# comm.net
KiCad netlist of a schematic drawn in EAGLE
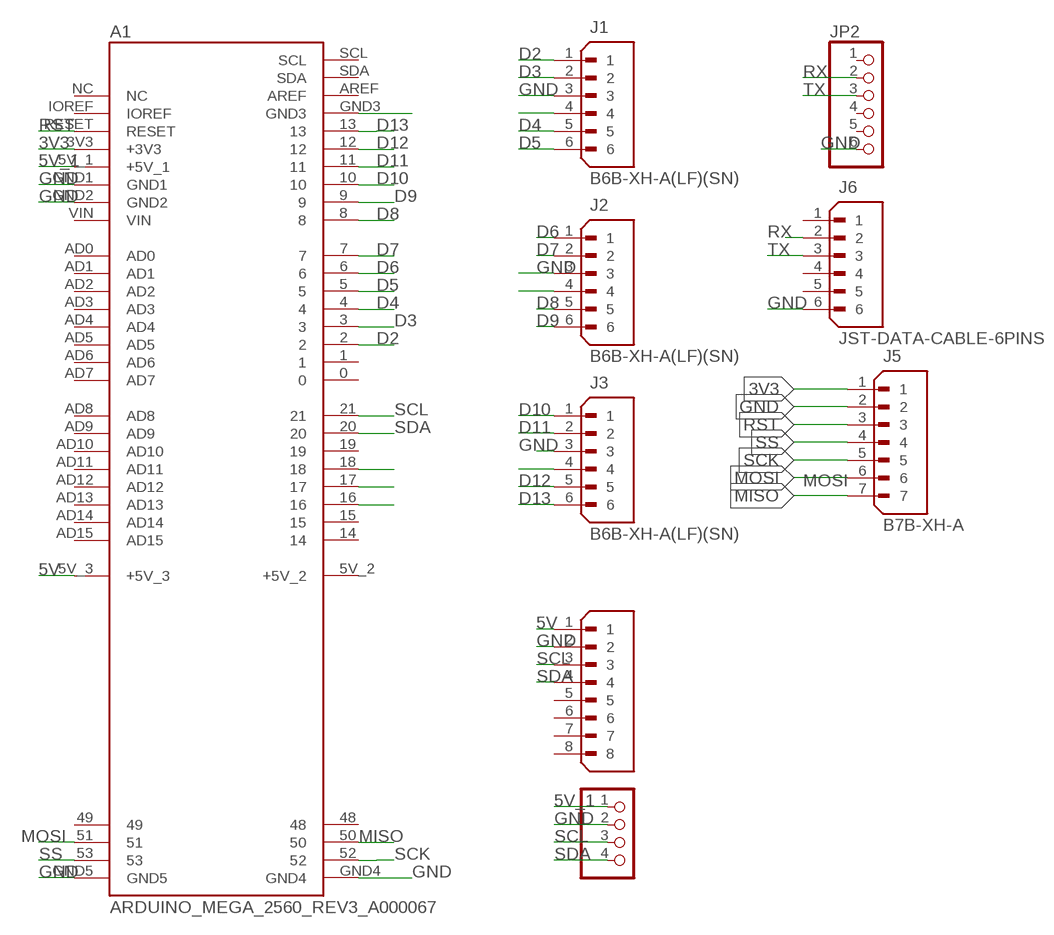
[diagram p0: schematic, sheet 1]

(export (version "E")
  (design (tool "Eeschema 10.0.6"))
  (components
    (comp (ref "A1")
      (value "ARDUINO_MEGA_2560_REV3_A000067")
      (footprint "eagle-import:ARDUINO_ARDUINO_MEGA_2560_REV3_A000067")
      (fields (field (name "MF") "Arduino") (field (name "MP") "ARDUINO MEGA 2560 REV3 | A000067"))
      (libsource (lib "eagle-import") (part "ARDUINO_MEGA_2560_REV3_A000067"))
    )
    (comp (ref "J1")
      (value "B6B-XH-A(LF)(SN)")
      (footprint "eagle-import:JST_B6B-XH-A(LF)(SN)")
      (fields (field (name "MF") "JST Sales") (field (name "MP") "B6B-XH-A (LF)(SN)"))
      (libsource (lib "eagle-import") (part "B6B-XH-A(LF)(SN)"))
    )
    (comp (ref "J2")
      (value "B6B-XH-A(LF)(SN)")
      (footprint "eagle-import:JST_B6B-XH-A(LF)(SN)")
      (fields (field (name "MF") "JST Sales") (field (name "MP") "B6B-XH-A (LF)(SN)"))
      (libsource (lib "eagle-import") (part "B6B-XH-A(LF)(SN)"))
    )
    (comp (ref "J3")
      (value "B6B-XH-A(LF)(SN)")
      (footprint "eagle-import:JST_B6B-XH-A(LF)(SN)")
      (fields (field (name "MF") "JST Sales") (field (name "MP") "B6B-XH-A (LF)(SN)"))
      (libsource (lib "eagle-import") (part "B6B-XH-A(LF)(SN)"))
    )
    (comp (ref "J4")
      (value "B8B-XH-A(LF)(SN)")
      (footprint "eagle-import:JST_B8B-XH-A(LF)(SN)")
      (fields (field (name "MF") "JST Sales") (field (name "MP") "B8B-XH-A (LF)(SN)"))
      (libsource (lib "eagle-import") (part "B8B-XH-A(LF)(SN)"))
    )
    (comp (ref "J5")
      (value "B7B-XH-A")
      (footprint "eagle-import:JST_B7B-XH-A")
      (fields (field (name "MF") "JST Sales"))
      (libsource (lib "eagle-import") (part "B7B-XH-A"))
    )
    (comp (ref "J6")
      (value "JST-DATA-CABLE-6PINS")
      (footprint "eagle-import:JST_B6B-XH-A(LF)(SN)")
      (fields (field (name "MF") "JST Sales") (field (name "MP") "B6B-XH-A (LF)(SN)"))
      (libsource (lib "eagle-import") (part "JST-DATA-CABLE-6PINS"))
    )
    (comp (ref "JP1")
      (value "PINHD-1X4")
      (footprint "eagle-import:1X04")
      (libsource (lib "eagle-import") (part "PINHD-1X4"))
    )
    (comp (ref "JP2")
      (value "PINHD-1X6")
      (footprint "eagle-import:1X06")
      (libsource (lib "eagle-import") (part "PINHD-1X6"))
    )
  )
  (nets
    (net (code "1") (name "/5V") (class "Default")
      (node (ref "A1") (pin "5V_3") (pinfunction "+5V_3_5V_3") (pintype "passive"))
      (node (ref "J4") (pin "1") (pinfunction "1_1") (pintype "passive"))
    )
    (net (code "2") (name "/5V_1") (class "Default")
      (node (ref "A1") (pin "5V_1") (pinfunction "+5V_1_5V_1") (pintype "passive"))
      (node (ref "JP1") (pin "1") (pinfunction "1_1") (pintype "passive"))
    )
    (net (code "3") (name "/D2") (class "Default")
      (node (ref "A1") (pin "2") (pinfunction "2_2") (pintype "passive"))
      (node (ref "J1") (pin "1") (pinfunction "1_1") (pintype "passive"))
    )
    (net (code "4") (name "/D3") (class "Default")
      (node (ref "A1") (pin "3") (pinfunction "3_3") (pintype "passive"))
      (node (ref "J1") (pin "2") (pinfunction "2_2") (pintype "passive"))
    )
    (net (code "5") (name "/D4") (class "Default")
      (node (ref "A1") (pin "4") (pinfunction "4_4") (pintype "passive"))
      (node (ref "J1") (pin "5") (pinfunction "5_5") (pintype "passive"))
    )
    (net (code "6") (name "/D5") (class "Default")
      (node (ref "A1") (pin "5") (pinfunction "5_5") (pintype "passive"))
      (node (ref "J1") (pin "6") (pinfunction "6_6") (pintype "passive"))
    )
    (net (code "7") (name "/D6") (class "Default")
      (node (ref "A1") (pin "6") (pinfunction "6_6") (pintype "passive"))
      (node (ref "J2") (pin "1") (pinfunction "1_1") (pintype "passive"))
    )
    (net (code "8") (name "/D7") (class "Default")
      (node (ref "A1") (pin "7") (pinfunction "7_7") (pintype "passive"))
      (node (ref "J2") (pin "2") (pinfunction "2_2") (pintype "passive"))
    )
    (net (code "9") (name "/D8") (class "Default")
      (node (ref "A1") (pin "8") (pinfunction "8_8") (pintype "passive"))
      (node (ref "J2") (pin "5") (pinfunction "5_5") (pintype "passive"))
    )
    (net (code "10") (name "/D9") (class "Default")
      (node (ref "A1") (pin "9") (pinfunction "9_9") (pintype "passive"))
      (node (ref "J2") (pin "6") (pinfunction "6_6") (pintype "passive"))
    )
    (net (code "11") (name "/D10") (class "Default")
      (node (ref "A1") (pin "10") (pinfunction "10_10") (pintype "passive"))
      (node (ref "J3") (pin "1") (pinfunction "1_1") (pintype "passive"))
    )
    (net (code "12") (name "/D11") (class "Default")
      (node (ref "A1") (pin "11") (pinfunction "11_11") (pintype "passive"))
      (node (ref "J3") (pin "2") (pinfunction "2_2") (pintype "passive"))
    )
    (net (code "13") (name "/D12") (class "Default")
      (node (ref "A1") (pin "12") (pinfunction "12_12") (pintype "passive"))
      (node (ref "J3") (pin "4") (pinfunction "4_4") (pintype "passive"))
      (node (ref "J3") (pin "5") (pinfunction "5_5") (pintype "passive"))
    )
    (net (code "14") (name "/D13") (class "Default")
      (node (ref "A1") (pin "13") (pinfunction "13_13") (pintype "passive"))
      (node (ref "J3") (pin "6") (pinfunction "6_6") (pintype "passive"))
    )
    (net (code "15") (name "/RX") (class "Default")
      (node (ref "J6") (pin "2") (pinfunction "2_2") (pintype "passive"))
      (node (ref "JP2") (pin "2") (pinfunction "2_2") (pintype "passive"))
    )
    (net (code "16") (name "/SCL") (class "Default")
      (node (ref "A1") (pin "21") (pinfunction "21_21") (pintype "passive"))
      (node (ref "J4") (pin "3") (pinfunction "3_3") (pintype "passive"))
      (node (ref "JP1") (pin "3") (pinfunction "3_3") (pintype "passive"))
    )
    (net (code "17") (name "/SDA") (class "Default")
      (node (ref "A1") (pin "20") (pinfunction "20_20") (pintype "passive"))
      (node (ref "J4") (pin "4") (pinfunction "4_4") (pintype "passive"))
      (node (ref "JP1") (pin "4") (pinfunction "4_4") (pintype "passive"))
    )
    (net (code "18") (name "/TX") (class "Default")
      (node (ref "J6") (pin "3") (pinfunction "3_3") (pintype "passive"))
      (node (ref "JP2") (pin "3") (pinfunction "3_3") (pintype "passive"))
    )
    (net (code "19") (name "3V3") (class "Default")
      (node (ref "A1") (pin "3V3") (pinfunction "+3V3_3V3") (pintype "passive"))
      (node (ref "J5") (pin "1") (pinfunction "1_1") (pintype "passive"))
    )
    (net (code "20") (name "GND") (class "Default")
      (node (ref "A1") (pin "GND1") (pinfunction "GND1_GND1") (pintype "passive"))
      (node (ref "A1") (pin "GND2") (pinfunction "GND2_GND2") (pintype "passive"))
      (node (ref "A1") (pin "GND4") (pinfunction "GND4_GND4") (pintype "passive"))
      (node (ref "A1") (pin "GND5") (pinfunction "GND5_GND5") (pintype "passive"))
      (node (ref "J1") (pin "3") (pinfunction "3_3") (pintype "passive"))
      (node (ref "J2") (pin "3") (pinfunction "3_3") (pintype "passive"))
      (node (ref "J3") (pin "3") (pinfunction "3_3") (pintype "passive"))
      (node (ref "J4") (pin "2") (pinfunction "2_2") (pintype "passive"))
      (node (ref "J5") (pin "2") (pinfunction "2_2") (pintype "passive"))
      (node (ref "J6") (pin "6") (pinfunction "6_6") (pintype "passive"))
      (node (ref "JP1") (pin "2") (pinfunction "2_2") (pintype "passive"))
      (node (ref "JP2") (pin "6") (pinfunction "6_6") (pintype "passive"))
    )
    (net (code "21") (name "MISO") (class "Default")
      (node (ref "A1") (pin "50") (pinfunction "50_50") (pintype "passive"))
      (node (ref "J5") (pin "7") (pinfunction "7_7") (pintype "passive"))
    )
    (net (code "22") (name "MOSI") (class "Default")
      (node (ref "A1") (pin "51") (pinfunction "51_51") (pintype "passive"))
      (node (ref "J5") (pin "6") (pinfunction "6_6") (pintype "passive"))
    )
    (net (code "23") (name "RST") (class "Default")
      (node (ref "A1") (pin "RESET") (pinfunction "RESET_RESET") (pintype "passive"))
      (node (ref "J5") (pin "3") (pinfunction "3_3") (pintype "passive"))
    )
    (net (code "24") (name "SCK") (class "Default")
      (node (ref "A1") (pin "52") (pinfunction "52_52") (pintype "passive"))
      (node (ref "J5") (pin "5") (pinfunction "5_5") (pintype "passive"))
    )
    (net (code "25") (name "SS") (class "Default")
      (node (ref "A1") (pin "53") (pinfunction "53_53") (pintype "passive"))
      (node (ref "J5") (pin "4") (pinfunction "4_4") (pintype "passive"))
    )
    (net (code "26") (name "unconnected-(A1-+5V_2-Pad5V_2)") (class "Default")
      (node (ref "A1") (pin "5V_2") (pinfunction "+5V_2_5V_2") (pintype "passive"))
    )
    (net (code "27") (name "unconnected-(A1-Pad0)") (class "Default")
      (node (ref "A1") (pin "0") (pinfunction "0_0") (pintype "passive"))
    )
    (net (code "28") (name "unconnected-(A1-Pad1)") (class "Default")
      (node (ref "A1") (pin "1") (pinfunction "1_1") (pintype "passive"))
    )
    (net (code "29") (name "unconnected-(A1-Pad14)") (class "Default")
      (node (ref "A1") (pin "14") (pinfunction "14_14") (pintype "passive"))
    )
    (net (code "30") (name "unconnected-(A1-Pad15)") (class "Default")
      (node (ref "A1") (pin "15") (pinfunction "15_15") (pintype "passive"))
    )
    (net (code "31") (name "unconnected-(A1-Pad16)") (class "Default")
      (node (ref "A1") (pin "16") (pinfunction "16_16") (pintype "passive"))
    )
    (net (code "32") (name "unconnected-(A1-Pad17)") (class "Default")
      (node (ref "A1") (pin "17") (pinfunction "17_17") (pintype "passive"))
    )
    (net (code "33") (name "unconnected-(A1-Pad18)") (class "Default")
      (node (ref "A1") (pin "18") (pinfunction "18_18") (pintype "passive"))
    )
    (net (code "34") (name "unconnected-(A1-Pad19)") (class "Default")
      (node (ref "A1") (pin "19") (pinfunction "19_19") (pintype "passive"))
    )
    (net (code "35") (name "unconnected-(A1-Pad48)") (class "Default")
      (node (ref "A1") (pin "48") (pinfunction "48_48") (pintype "passive"))
    )
    (net (code "36") (name "unconnected-(A1-Pad49)") (class "Default")
      (node (ref "A1") (pin "49") (pinfunction "49_49") (pintype "passive"))
    )
    (net (code "37") (name "unconnected-(A1-PadAD0)") (class "Default")
      (node (ref "A1") (pin "AD0") (pinfunction "AD0_AD0") (pintype "passive"))
    )
    (net (code "38") (name "unconnected-(A1-PadAD1)") (class "Default")
      (node (ref "A1") (pin "AD1") (pinfunction "AD1_AD1") (pintype "passive"))
    )
    (net (code "39") (name "unconnected-(A1-PadAD2)") (class "Default")
      (node (ref "A1") (pin "AD2") (pinfunction "AD2_AD2") (pintype "passive"))
    )
    (net (code "40") (name "unconnected-(A1-PadAD3)") (class "Default")
      (node (ref "A1") (pin "AD3") (pinfunction "AD3_AD3") (pintype "passive"))
    )
    (net (code "41") (name "unconnected-(A1-PadAD4)") (class "Default")
      (node (ref "A1") (pin "AD4") (pinfunction "AD4_AD4") (pintype "passive"))
    )
    (net (code "42") (name "unconnected-(A1-PadAD5)") (class "Default")
      (node (ref "A1") (pin "AD5") (pinfunction "AD5_AD5") (pintype "passive"))
    )
    (net (code "43") (name "unconnected-(A1-PadAD6)") (class "Default")
      (node (ref "A1") (pin "AD6") (pinfunction "AD6_AD6") (pintype "passive"))
    )
    (net (code "44") (name "unconnected-(A1-PadAD7)") (class "Default")
      (node (ref "A1") (pin "AD7") (pinfunction "AD7_AD7") (pintype "passive"))
    )
    (net (code "45") (name "unconnected-(A1-PadAD8)") (class "Default")
      (node (ref "A1") (pin "AD8") (pinfunction "AD8_AD8") (pintype "passive"))
    )
    (net (code "46") (name "unconnected-(A1-PadAD9)") (class "Default")
      (node (ref "A1") (pin "AD9") (pinfunction "AD9_AD9") (pintype "passive"))
    )
    (net (code "47") (name "unconnected-(A1-PadAD10)") (class "Default")
      (node (ref "A1") (pin "AD10") (pinfunction "AD10_AD10") (pintype "passive"))
    )
    (net (code "48") (name "unconnected-(A1-PadAD11)") (class "Default")
      (node (ref "A1") (pin "AD11") (pinfunction "AD11_AD11") (pintype "passive"))
    )
    (net (code "49") (name "unconnected-(A1-PadAD12)") (class "Default")
      (node (ref "A1") (pin "AD12") (pinfunction "AD12_AD12") (pintype "passive"))
    )
    (net (code "50") (name "unconnected-(A1-PadAD13)") (class "Default")
      (node (ref "A1") (pin "AD13") (pinfunction "AD13_AD13") (pintype "passive"))
    )
    (net (code "51") (name "unconnected-(A1-PadAD14)") (class "Default")
      (node (ref "A1") (pin "AD14") (pinfunction "AD14_AD14") (pintype "passive"))
    )
    (net (code "52") (name "unconnected-(A1-PadAD15)") (class "Default")
      (node (ref "A1") (pin "AD15") (pinfunction "AD15_AD15") (pintype "passive"))
    )
    (net (code "53") (name "unconnected-(A1-PadAREF)") (class "Default")
      (node (ref "A1") (pin "AREF") (pinfunction "AREF_AREF") (pintype "passive"))
    )
    (net (code "54") (name "unconnected-(A1-PadGND3)") (class "Default")
      (node (ref "A1") (pin "GND3") (pinfunction "GND3_GND3") (pintype "passive"))
    )
    (net (code "55") (name "unconnected-(A1-PadIOREF)") (class "Default")
      (node (ref "A1") (pin "IOREF") (pinfunction "IOREF_IOREF") (pintype "passive"))
    )
    (net (code "56") (name "unconnected-(A1-PadNC)") (class "Default")
      (node (ref "A1") (pin "NC") (pinfunction "NC_NC") (pintype "passive"))
    )
    (net (code "57") (name "unconnected-(A1-PadSCL)") (class "Default")
      (node (ref "A1") (pin "SCL") (pinfunction "SCL_SCL") (pintype "passive"))
    )
    (net (code "58") (name "unconnected-(A1-PadSDA)") (class "Default")
      (node (ref "A1") (pin "SDA") (pinfunction "SDA_SDA") (pintype "passive"))
    )
    (net (code "59") (name "unconnected-(A1-PadVIN)") (class "Default")
      (node (ref "A1") (pin "VIN") (pinfunction "VIN_VIN") (pintype "passive"))
    )
    (net (code "60") (name "unconnected-(J1-Pad4)") (class "Default")
      (node (ref "J1") (pin "4") (pinfunction "4_4") (pintype "passive"))
    )
    (net (code "61") (name "unconnected-(J2-Pad4)") (class "Default")
      (node (ref "J2") (pin "4") (pinfunction "4_4") (pintype "passive"))
    )
    (net (code "62") (name "unconnected-(J4-Pad5)") (class "Default")
      (node (ref "J4") (pin "5") (pinfunction "5_5") (pintype "passive"))
    )
    (net (code "63") (name "unconnected-(J4-Pad6)") (class "Default")
      (node (ref "J4") (pin "6") (pinfunction "6_6") (pintype "passive"))
    )
    (net (code "64") (name "unconnected-(J4-Pad7)") (class "Default")
      (node (ref "J4") (pin "7") (pinfunction "7_7") (pintype "passive"))
    )
    (net (code "65") (name "unconnected-(J4-Pad8)") (class "Default")
      (node (ref "J4") (pin "8") (pinfunction "8_8") (pintype "passive"))
    )
    (net (code "66") (name "unconnected-(J6-Pad1)") (class "Default")
      (node (ref "J6") (pin "1") (pinfunction "1_1") (pintype "passive"))
    )
    (net (code "67") (name "unconnected-(J6-Pad4)") (class "Default")
      (node (ref "J6") (pin "4") (pinfunction "4_4") (pintype "passive"))
    )
    (net (code "68") (name "unconnected-(J6-Pad5)") (class "Default")
      (node (ref "J6") (pin "5") (pinfunction "5_5") (pintype "passive"))
    )
    (net (code "69") (name "unconnected-(JP2-Pad1)") (class "Default")
      (node (ref "JP2") (pin "1") (pinfunction "1_1") (pintype "passive"))
    )
    (net (code "70") (name "unconnected-(JP2-Pad4)") (class "Default")
      (node (ref "JP2") (pin "4") (pinfunction "4_4") (pintype "passive"))
    )
    (net (code "71") (name "unconnected-(JP2-Pad5)") (class "Default")
      (node (ref "JP2") (pin "5") (pinfunction "5_5") (pintype "passive"))
    )
  )
)
